# EEZ_DIB_BP3C_r3B3.net
KiCad netlist of a schematic drawn in EAGLE
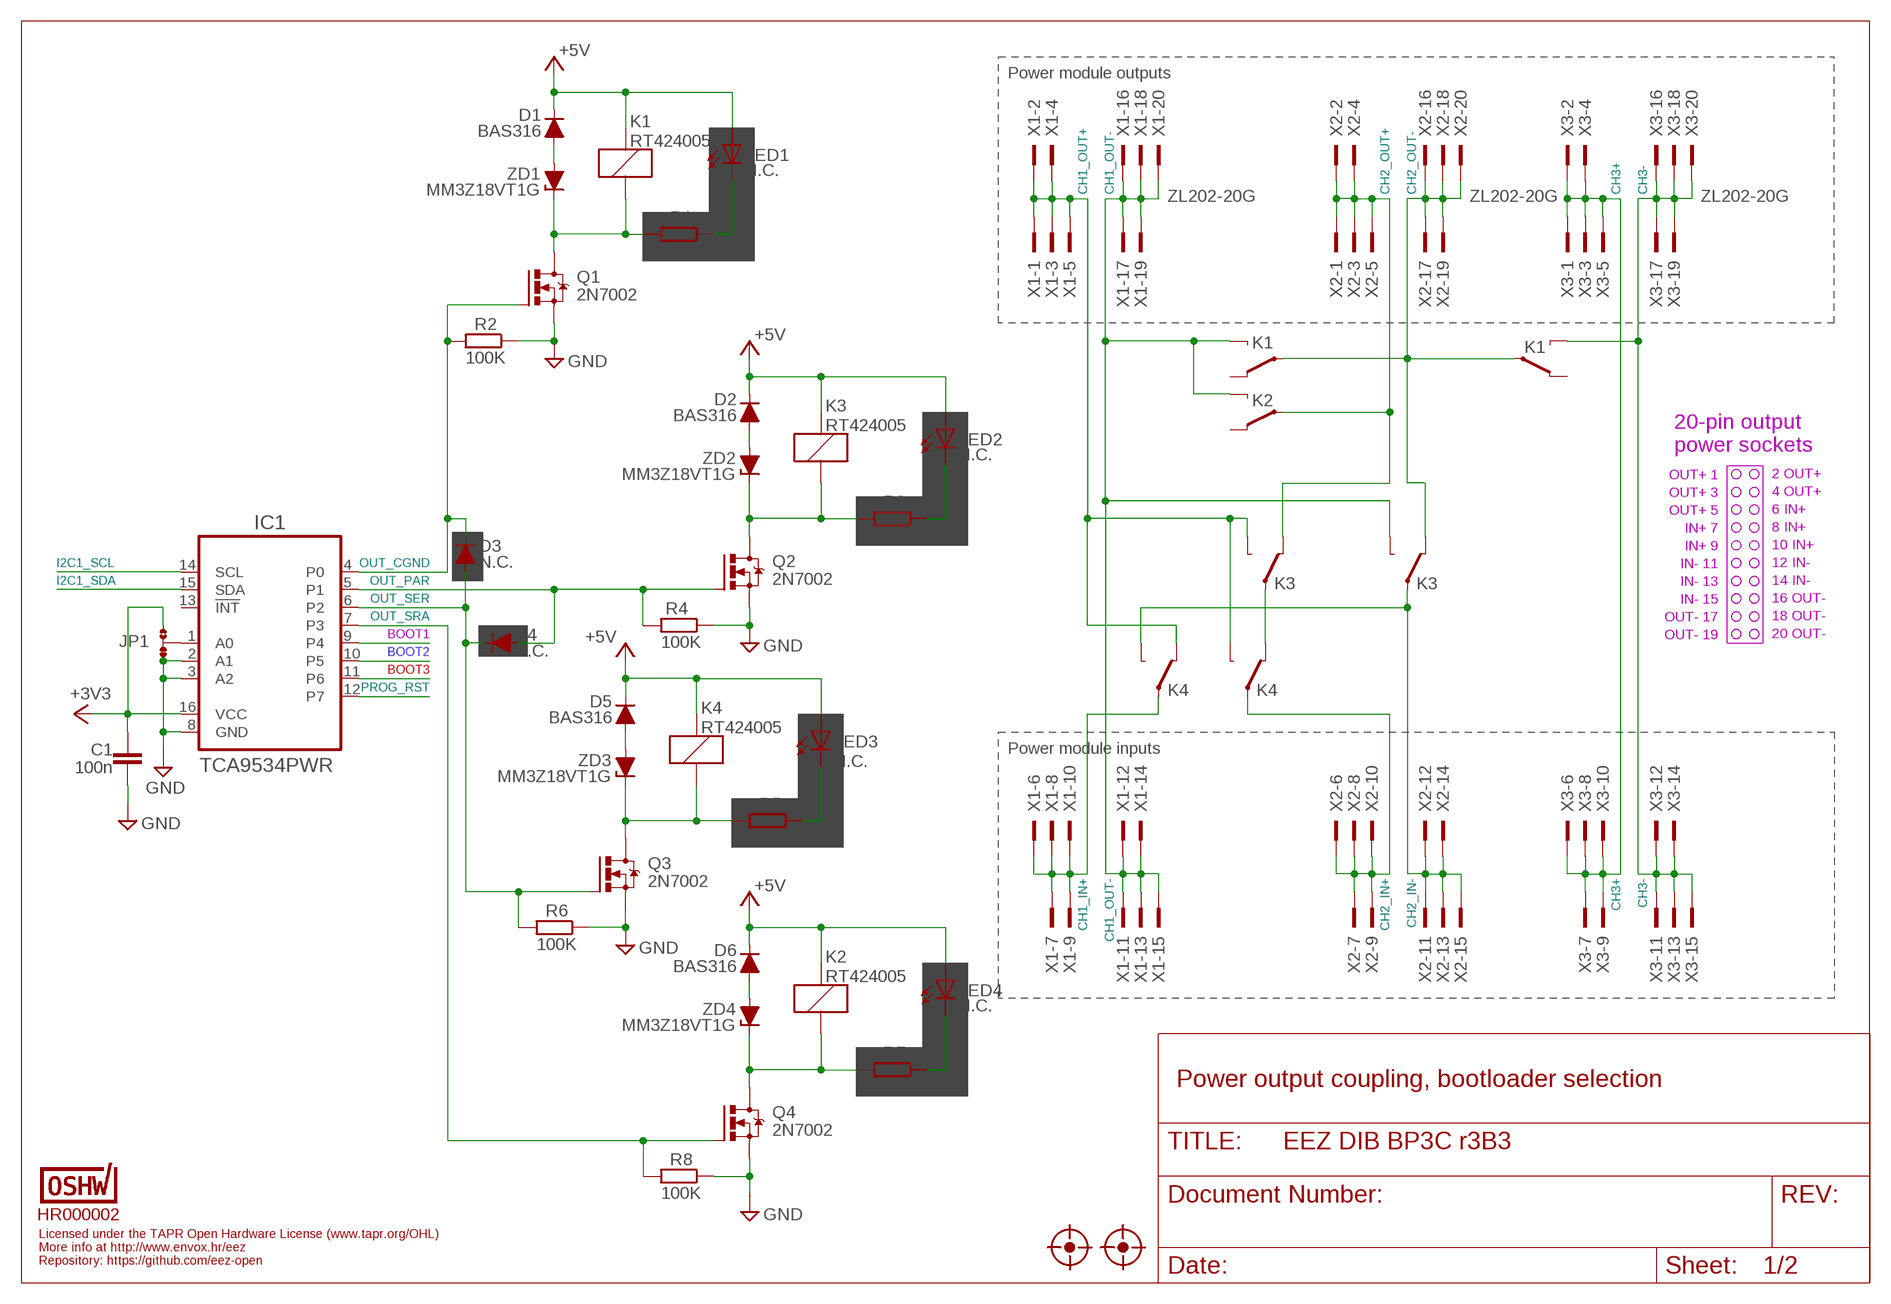
[diagram p0: schematic, sheet 1]
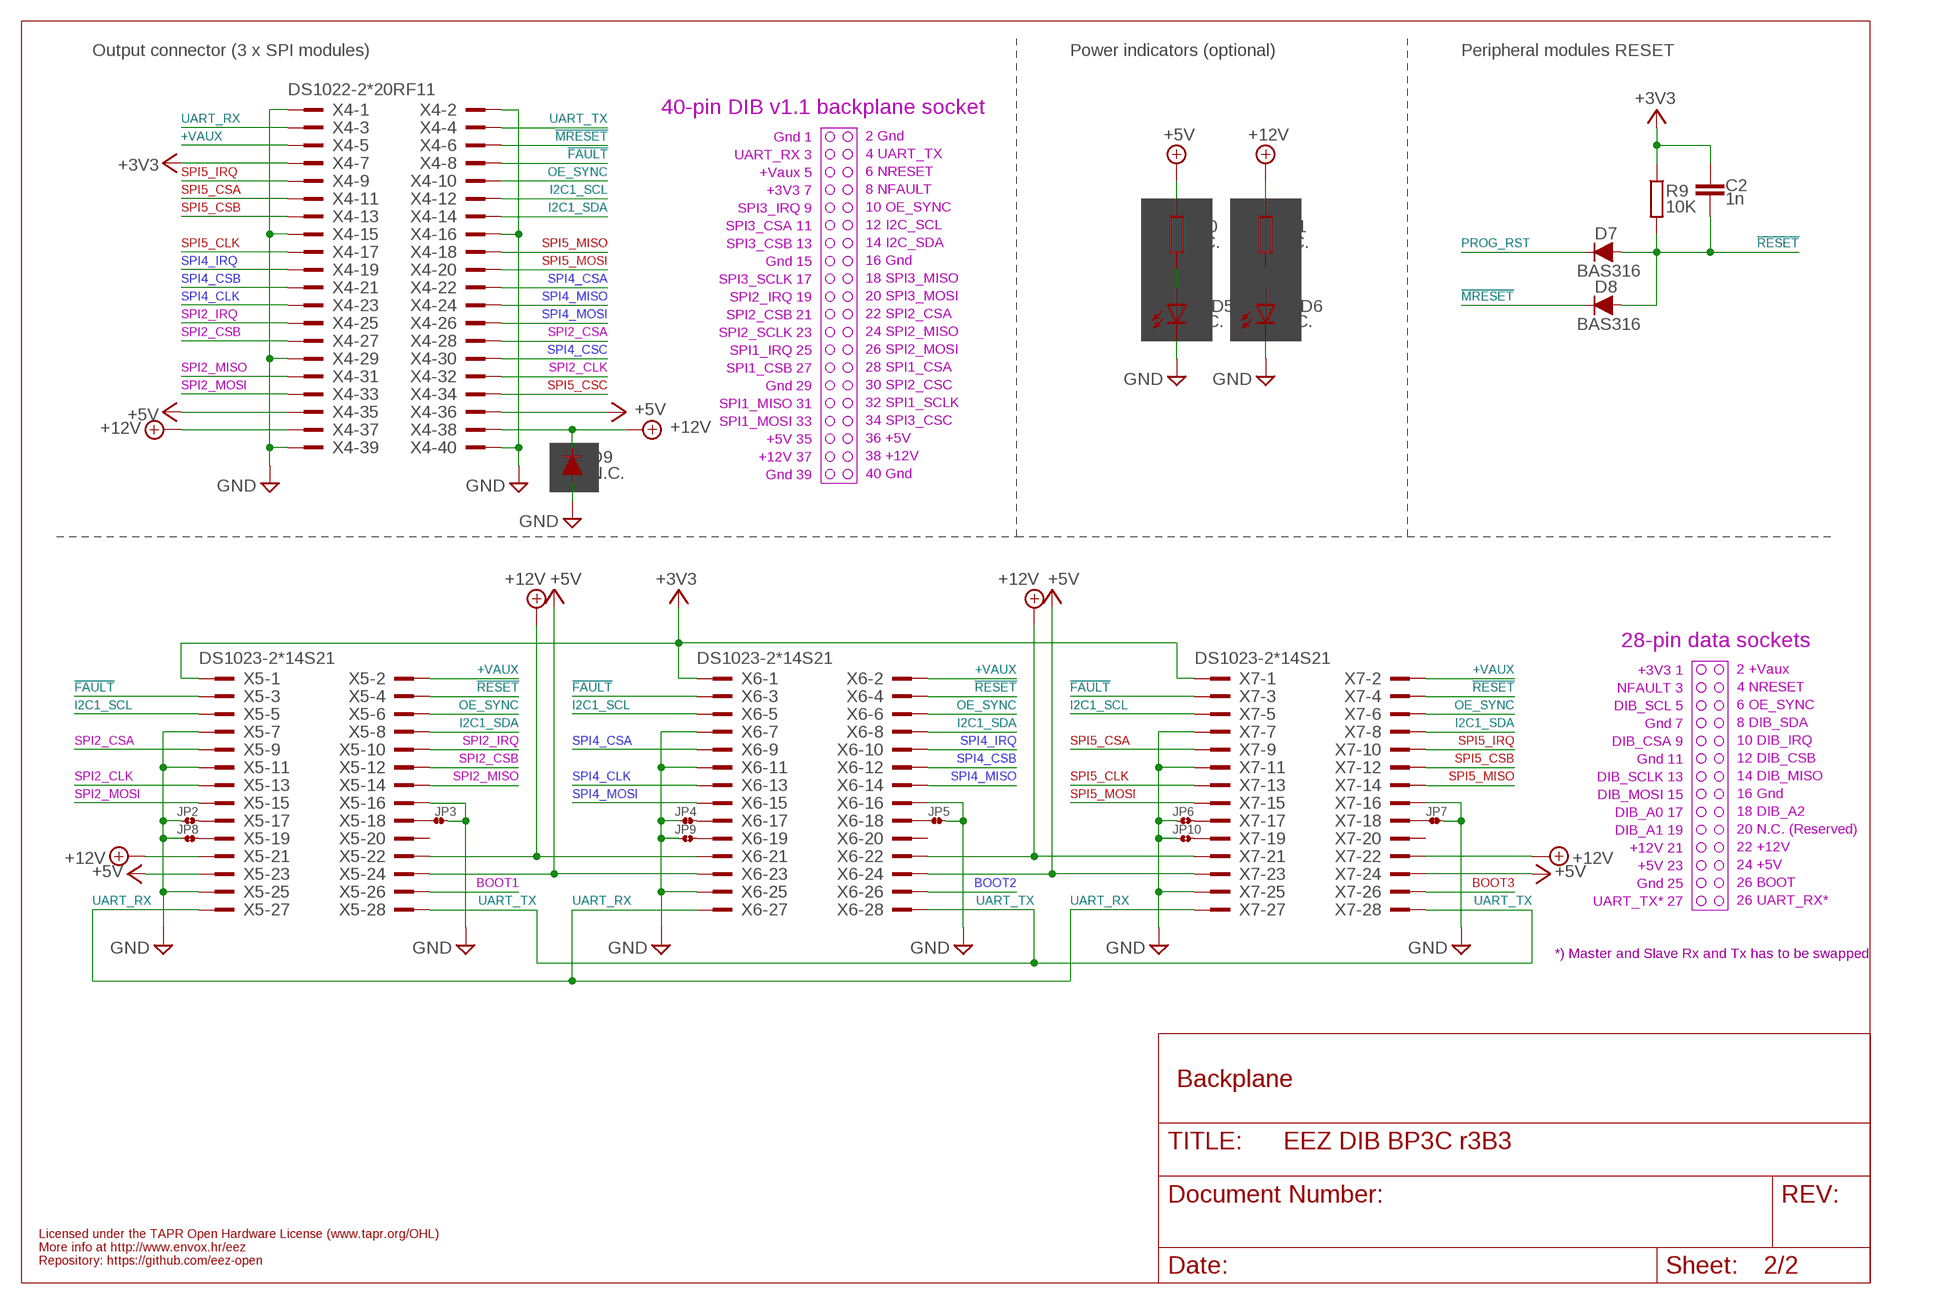
[diagram p1: schematic, sheet 2]

(export (version "E")
  (design (tool "Eeschema 10.0.6"))
  (components
    (comp (ref "C1")
      (value "100n")
      (footprint "eagle-import:C0603")
      (libsource (lib "eagle-import") (part "C-EUC0603"))
    )
    (comp (ref "D1")
      (value "BAS316")
      (footprint "eagle-import:SOD323-R")
      (libsource (lib "eagle-import") (part "DIODESOD323R"))
    )
    (comp (ref "D2")
      (value "BAS316")
      (footprint "eagle-import:SOD323-R")
      (libsource (lib "eagle-import") (part "DIODESOD323R"))
    )
    (comp (ref "D3")
      (value "N.C.")
      (footprint "eagle-import:SOD323-R")
      (libsource (lib "eagle-import") (part "DIODESOD323R"))
    )
    (comp (ref "D4")
      (value "N.C.")
      (footprint "eagle-import:SOD323-R")
      (libsource (lib "eagle-import") (part "DIODESOD323R"))
    )
    (comp (ref "D5")
      (value "BAS316")
      (footprint "eagle-import:SOD323-R")
      (libsource (lib "eagle-import") (part "DIODESOD323R"))
    )
    (comp (ref "D6")
      (value "BAS316")
      (footprint "eagle-import:SOD323-R")
      (libsource (lib "eagle-import") (part "DIODESOD323R"))
    )
    (comp (ref "FM1")
      (value "FIDUCIAL")
      (footprint "eagle-import:FIDUCIAL")
      (libsource (lib "eagle-import") (part "FIDUCIAL"))
    )
    (comp (ref "FM2")
      (value "FIDUCIAL")
      (footprint "eagle-import:FIDUCIAL")
      (libsource (lib "eagle-import") (part "FIDUCIAL"))
    )
    (comp (ref "IC1")
      (value "TCA9534PWR")
      (footprint "eagle-import:PW(R-PDSO-G16)")
      (libsource (lib "eagle-import") (part "TCA9534PWR"))
    )
    (comp (ref "JP1")
      (value "JP3-CUT")
      (footprint "eagle-import:JP3-CUT")
      (libsource (lib "eagle-import") (part "JP3-CUT"))
    )
    (comp (ref "K1")
      (value "RT424005")
      (footprint "eagle-import:RT-C_016A5_ROUND")
      (libsource (lib "eagle-import") (part "RELAY_RT314012-2"))
    )
    (comp (ref "K2")
      (value "RT424005")
      (footprint "eagle-import:RT-C_016A5_ROUND")
      (libsource (lib "eagle-import") (part "RELAY_RT314012-2"))
    )
    (comp (ref "K3")
      (value "RT424005")
      (footprint "eagle-import:RT-C_016A5_ROUND")
      (libsource (lib "eagle-import") (part "RELAY_RT314012-2"))
    )
    (comp (ref "K4")
      (value "RT424005")
      (footprint "eagle-import:RT-C_016A5_ROUND")
      (libsource (lib "eagle-import") (part "RELAY_RT314012-2"))
    )
    (comp (ref "LABEL1")
      (value "HR000002")
      (footprint "eagle-import:CERT-SMALL-SILK")
      (libsource (lib "eagle-import") (part "OSHWA-CERT-SMALL"))
    )
    (comp (ref "LED1")
      (value "N.C.")
      (footprint "eagle-import:LED_0805")
      (libsource (lib "eagle-import") (part "LED0805"))
    )
    (comp (ref "LED2")
      (value "N.C.")
      (footprint "eagle-import:LED_0805")
      (libsource (lib "eagle-import") (part "LED0805"))
    )
    (comp (ref "LED3")
      (value "N.C.")
      (footprint "eagle-import:LED_0805")
      (libsource (lib "eagle-import") (part "LED0805"))
    )
    (comp (ref "LED4")
      (value "N.C.")
      (footprint "eagle-import:LED_0805")
      (libsource (lib "eagle-import") (part "LED0805"))
    )
    (comp (ref "Q1")
      (value "2N7002")
      (footprint "eagle-import:SOT103P240X110-3N")
      (fields
        (field (name "MPN") "2N7002-7-F")
        (field (name "MPN_1") "2N7002-7-F")
        (field (name "OC_FARNELL") "1713823")
        (field (name "OC_NEWARK") "25R5679")
        (field (name "PACKAGE") "SOT-23-3")
        (field (name "SUPPLIER") "DIODES INC.")
      )
      (libsource (lib "eagle-import") (part "2N7002"))
    )
    (comp (ref "Q2")
      (value "2N7002")
      (footprint "eagle-import:SOT103P240X110-3N")
      (fields
        (field (name "MPN") "2N7002-7-F")
        (field (name "MPN_1") "2N7002-7-F")
        (field (name "OC_FARNELL") "1713823")
        (field (name "OC_NEWARK") "25R5679")
        (field (name "PACKAGE") "SOT-23-3")
        (field (name "SUPPLIER") "DIODES INC.")
      )
      (libsource (lib "eagle-import") (part "2N7002"))
    )
    (comp (ref "Q3")
      (value "2N7002")
      (footprint "eagle-import:SOT103P240X110-3N")
      (fields
        (field (name "MPN") "2N7002-7-F")
        (field (name "MPN_1") "2N7002-7-F")
        (field (name "OC_FARNELL") "1713823")
        (field (name "OC_NEWARK") "25R5679")
        (field (name "PACKAGE") "SOT-23-3")
        (field (name "SUPPLIER") "DIODES INC.")
      )
      (libsource (lib "eagle-import") (part "2N7002"))
    )
    (comp (ref "Q4")
      (value "2N7002")
      (footprint "eagle-import:SOT103P240X110-3N")
      (fields
        (field (name "MPN") "2N7002-7-F")
        (field (name "MPN_1") "2N7002-7-F")
        (field (name "OC_FARNELL") "1713823")
        (field (name "OC_NEWARK") "25R5679")
        (field (name "PACKAGE") "SOT-23-3")
        (field (name "SUPPLIER") "DIODES INC.")
      )
      (libsource (lib "eagle-import") (part "2N7002"))
    )
    (comp (ref "R1")
      (value "N.C.")
      (footprint "eagle-import:R0805")
      (libsource (lib "eagle-import") (part "R-EU_R0805"))
    )
    (comp (ref "R2")
      (value "100K")
      (footprint "eagle-import:R0805")
      (libsource (lib "eagle-import") (part "R-EU_R0805"))
    )
    (comp (ref "R3")
      (value "N.C.")
      (footprint "eagle-import:R0805")
      (libsource (lib "eagle-import") (part "R-EU_R0805"))
    )
    (comp (ref "R4")
      (value "100K")
      (footprint "eagle-import:R0805")
      (libsource (lib "eagle-import") (part "R-EU_R0805"))
    )
    (comp (ref "R5")
      (value "N.C.")
      (footprint "eagle-import:R0805")
      (libsource (lib "eagle-import") (part "R-EU_R0805"))
    )
    (comp (ref "R6")
      (value "100K")
      (footprint "eagle-import:R0805")
      (libsource (lib "eagle-import") (part "R-EU_R0805"))
    )
    (comp (ref "R7")
      (value "N.C.")
      (footprint "eagle-import:R0805")
      (libsource (lib "eagle-import") (part "R-EU_R0805"))
    )
    (comp (ref "R8")
      (value "100K")
      (footprint "eagle-import:R0805")
      (libsource (lib "eagle-import") (part "R-EU_R0805"))
    )
    (comp (ref "X1")
      (value "ZL202-20G")
      (footprint "eagle-import:DS1021-2_10SF11")
      (libsource (lib "eagle-import") (part "DS1021-210SF11"))
    )
    (comp (ref "X2")
      (value "ZL202-20G")
      (footprint "eagle-import:DS1021-2_10SF11")
      (libsource (lib "eagle-import") (part "DS1021-210SF11"))
    )
    (comp (ref "X3")
      (value "ZL202-20G")
      (footprint "eagle-import:DS1021-2_10SF11")
      (libsource (lib "eagle-import") (part "DS1021-210SF11"))
    )
    (comp (ref "ZD1")
      (value "MM3Z18VT1G")
      (footprint "eagle-import:SOD323-R")
      (libsource (lib "eagle-import") (part "ZENER-DIODESOD323R"))
    )
    (comp (ref "ZD2")
      (value "MM3Z18VT1G")
      (footprint "eagle-import:SOD323-R")
      (libsource (lib "eagle-import") (part "ZENER-DIODESOD323R"))
    )
    (comp (ref "ZD3")
      (value "MM3Z18VT1G")
      (footprint "eagle-import:SOD323-R")
      (libsource (lib "eagle-import") (part "ZENER-DIODESOD323R"))
    )
    (comp (ref "ZD4")
      (value "MM3Z18VT1G")
      (footprint "eagle-import:SOD323-R")
      (libsource (lib "eagle-import") (part "ZENER-DIODESOD323R"))
    )
    (comp (ref "C2")
      (value "1n")
      (footprint "eagle-import:C0805")
      (libsource (lib "eagle-import") (part "C-EUC0805"))
    )
    (comp (ref "D7")
      (value "BAS316")
      (footprint "eagle-import:SOD323-R")
      (libsource (lib "eagle-import") (part "DIODESOD323R"))
    )
    (comp (ref "D8")
      (value "BAS316")
      (footprint "eagle-import:SOD323-R")
      (libsource (lib "eagle-import") (part "DIODESOD323R"))
    )
    (comp (ref "D9")
      (value "N.C.")
      (footprint "eagle-import:DO214AA")
      (libsource (lib "eagle-import") (part "MyLib6_DIODEDO214AA"))
    )
    (comp (ref "JP2")
      (value "JP2-CUT")
      (footprint "eagle-import:JP2-CUT")
      (libsource (lib "eagle-import") (part "JP2-CUT"))
    )
    (comp (ref "JP3")
      (value "JP2-NOCUT")
      (footprint "eagle-import:JP2-NOCUT")
      (libsource (lib "eagle-import") (part "JP2-NOCUT"))
    )
    (comp (ref "JP4")
      (value "JP2-NOCUT")
      (footprint "eagle-import:JP2-NOCUT")
      (libsource (lib "eagle-import") (part "JP2-NOCUT"))
    )
    (comp (ref "JP5")
      (value "JP2-NOCUT")
      (footprint "eagle-import:JP2-NOCUT")
      (libsource (lib "eagle-import") (part "JP2-NOCUT"))
    )
    (comp (ref "JP6")
      (value "JP2-CUT")
      (footprint "eagle-import:JP2-CUT")
      (libsource (lib "eagle-import") (part "JP2-CUT"))
    )
    (comp (ref "JP7")
      (value "JP2-NOCUT")
      (footprint "eagle-import:JP2-NOCUT")
      (libsource (lib "eagle-import") (part "JP2-NOCUT"))
    )
    (comp (ref "JP8")
      (value "JP2-NOCUT")
      (footprint "eagle-import:JP2-NOCUT")
      (libsource (lib "eagle-import") (part "JP2-NOCUT"))
    )
    (comp (ref "JP9")
      (value "JP2-CUT")
      (footprint "eagle-import:JP2-CUT")
      (libsource (lib "eagle-import") (part "JP2-CUT"))
    )
    (comp (ref "JP10")
      (value "JP2-CUT")
      (footprint "eagle-import:JP2-CUT")
      (libsource (lib "eagle-import") (part "JP2-CUT"))
    )
    (comp (ref "LED5")
      (value "N.C.")
      (footprint "eagle-import:LED_0805")
      (libsource (lib "eagle-import") (part "LED0805"))
    )
    (comp (ref "LED6")
      (value "N.C.")
      (footprint "eagle-import:LED_0805")
      (libsource (lib "eagle-import") (part "LED0805"))
    )
    (comp (ref "R9")
      (value "10K")
      (footprint "eagle-import:R0805")
      (libsource (lib "eagle-import") (part "R-EU_R0805"))
    )
    (comp (ref "R10")
      (value "N.C.")
      (footprint "eagle-import:R0805")
      (libsource (lib "eagle-import") (part "R-EU_R0805"))
    )
    (comp (ref "R11")
      (value "N.C.")
      (footprint "eagle-import:R0805")
      (libsource (lib "eagle-import") (part "R-EU_R0805"))
    )
    (comp (ref "X4")
      (value "DS1022-2*20RF11")
      (footprint "eagle-import:ZL212-40KG")
      (libsource (lib "eagle-import") (part "ZL212-40KG"))
    )
    (comp (ref "X5")
      (value "DS1023-2*14S21")
      (footprint "eagle-import:TSW-114-07-F-D")
      (libsource (lib "eagle-import") (part "TSW-114-07-F-D"))
    )
    (comp (ref "X6")
      (value "DS1023-2*14S21")
      (footprint "eagle-import:TSW-114-07-F-D")
      (libsource (lib "eagle-import") (part "TSW-114-07-F-D"))
    )
    (comp (ref "X7")
      (value "DS1023-2*14S21")
      (footprint "eagle-import:TSW-114-07-F-D")
      (libsource (lib "eagle-import") (part "TSW-114-07-F-D"))
    )
  )
  (nets
    (net (code "1") (name "+3V3") (class "Default")
      (node (ref "C1") (pin "1") (pinfunction "1_1") (pintype "passive"))
      (node (ref "C2") (pin "2") (pinfunction "2_2") (pintype "passive"))
      (node (ref "IC1") (pin "16") (pinfunction "VCC_16") (pintype "passive"))
      (node (ref "JP1") (pin "NO") (pinfunction "NO_NO") (pintype "passive"))
      (node (ref "R9") (pin "1") (pinfunction "1_1") (pintype "passive"))
      (node (ref "X4") (pin "7") (pinfunction "1_7") (pintype "passive"))
      (node (ref "X5") (pin "1") (pinfunction "1_1") (pintype "passive"))
      (node (ref "X6") (pin "1") (pinfunction "1_1") (pintype "passive"))
      (node (ref "X7") (pin "1") (pinfunction "1_1") (pintype "passive"))
    )
    (net (code "2") (name "+5V") (class "Default")
      (node (ref "D1") (pin "C") (pinfunction "C_C") (pintype "passive"))
      (node (ref "D2") (pin "C") (pinfunction "C_C") (pintype "passive"))
      (node (ref "D5") (pin "C") (pinfunction "C_C") (pintype "passive"))
      (node (ref "D6") (pin "C") (pinfunction "C_C") (pintype "passive"))
      (node (ref "K1") (pin "A2") (pinfunction "C1_A2") (pintype "passive"))
      (node (ref "K2") (pin "A2") (pinfunction "C1_A2") (pintype "passive"))
      (node (ref "K3") (pin "A2") (pinfunction "C1_A2") (pintype "passive"))
      (node (ref "K4") (pin "A2") (pinfunction "C1_A2") (pintype "passive"))
      (node (ref "LED1") (pin "A") (pinfunction "A_A") (pintype "passive"))
      (node (ref "LED2") (pin "A") (pinfunction "A_A") (pintype "passive"))
      (node (ref "LED3") (pin "A") (pinfunction "A_A") (pintype "passive"))
      (node (ref "LED4") (pin "A") (pinfunction "A_A") (pintype "passive"))
      (node (ref "R10") (pin "1") (pinfunction "1_1") (pintype "passive"))
      (node (ref "X4") (pin "35") (pinfunction "1_35") (pintype "passive"))
      (node (ref "X4") (pin "36") (pinfunction "1_36") (pintype "passive"))
      (node (ref "X5") (pin "23") (pinfunction "1_23") (pintype "passive"))
      (node (ref "X5") (pin "24") (pinfunction "1_24") (pintype "passive"))
      (node (ref "X6") (pin "23") (pinfunction "1_23") (pintype "passive"))
      (node (ref "X6") (pin "24") (pinfunction "1_24") (pintype "passive"))
      (node (ref "X7") (pin "23") (pinfunction "1_23") (pintype "passive"))
      (node (ref "X7") (pin "24") (pinfunction "1_24") (pintype "passive"))
    )
    (net (code "3") (name "+12V") (class "Default")
      (node (ref "D9") (pin "C") (pinfunction "C_C") (pintype "passive"))
      (node (ref "R11") (pin "1") (pinfunction "1_1") (pintype "passive"))
      (node (ref "X4") (pin "37") (pinfunction "1_37") (pintype "passive"))
      (node (ref "X4") (pin "38") (pinfunction "1_38") (pintype "passive"))
      (node (ref "X5") (pin "21") (pinfunction "1_21") (pintype "passive"))
      (node (ref "X5") (pin "22") (pinfunction "1_22") (pintype "passive"))
      (node (ref "X6") (pin "21") (pinfunction "1_21") (pintype "passive"))
      (node (ref "X6") (pin "22") (pinfunction "1_22") (pintype "passive"))
      (node (ref "X7") (pin "21") (pinfunction "1_21") (pintype "passive"))
      (node (ref "X7") (pin "22") (pinfunction "1_22") (pintype "passive"))
    )
    (net (code "4") (name "+VAUX") (class "Default")
      (node (ref "X4") (pin "5") (pinfunction "1_5") (pintype "passive"))
      (node (ref "X5") (pin "2") (pinfunction "1_2") (pintype "passive"))
      (node (ref "X6") (pin "2") (pinfunction "1_2") (pintype "passive"))
      (node (ref "X7") (pin "2") (pinfunction "1_2") (pintype "passive"))
    )
    (net (code "5") (name "BOOT1") (class "Default")
      (node (ref "IC1") (pin "9") (pinfunction "P4_9") (pintype "bidirectional"))
      (node (ref "X5") (pin "26") (pinfunction "1_26") (pintype "passive"))
    )
    (net (code "6") (name "BOOT2") (class "Default")
      (node (ref "IC1") (pin "10") (pinfunction "P5_10") (pintype "bidirectional"))
      (node (ref "X6") (pin "26") (pinfunction "1_26") (pintype "passive"))
    )
    (net (code "7") (name "BOOT3") (class "Default")
      (node (ref "IC1") (pin "11") (pinfunction "P6_11") (pintype "bidirectional"))
      (node (ref "X7") (pin "26") (pinfunction "1_26") (pintype "passive"))
    )
    (net (code "8") (name "CH1_IN+") (class "Default")
      (node (ref "K4") (pin "11A") (pinfunction "P_11A") (pintype "passive"))
      (node (ref "X1") (pin "10") (pinfunction "1_10") (pintype "passive"))
      (node (ref "X1") (pin "6") (pinfunction "1_6") (pintype "passive"))
      (node (ref "X1") (pin "7") (pinfunction "1_7") (pintype "passive"))
      (node (ref "X1") (pin "8") (pinfunction "1_8") (pintype "passive"))
      (node (ref "X1") (pin "9") (pinfunction "1_9") (pintype "passive"))
    )
    (net (code "9") (name "CH1_OUT+") (class "Default")
      (node (ref "K3") (pin "14A") (pinfunction "O_14A") (pintype "passive"))
      (node (ref "K4") (pin "12A") (pinfunction "S_12A") (pintype "passive"))
      (node (ref "K4") (pin "14B") (pinfunction "O_14B") (pintype "passive"))
      (node (ref "X1") (pin "1") (pinfunction "1_1") (pintype "passive"))
      (node (ref "X1") (pin "2") (pinfunction "1_2") (pintype "passive"))
      (node (ref "X1") (pin "3") (pinfunction "1_3") (pintype "passive"))
      (node (ref "X1") (pin "4") (pinfunction "1_4") (pintype "passive"))
      (node (ref "X1") (pin "5") (pinfunction "1_5") (pintype "passive"))
    )
    (net (code "10") (name "CH1_OUT-") (class "Default")
      (node (ref "K1") (pin "14A") (pinfunction "O_14A") (pintype "passive"))
      (node (ref "K2") (pin "14A") (pinfunction "O_14A") (pintype "passive"))
      (node (ref "K3") (pin "14B") (pinfunction "O_14B") (pintype "passive"))
      (node (ref "X1") (pin "11") (pinfunction "1_11") (pintype "passive"))
      (node (ref "X1") (pin "12") (pinfunction "1_12") (pintype "passive"))
      (node (ref "X1") (pin "13") (pinfunction "1_13") (pintype "passive"))
      (node (ref "X1") (pin "14") (pinfunction "1_14") (pintype "passive"))
      (node (ref "X1") (pin "15") (pinfunction "1_15") (pintype "passive"))
      (node (ref "X1") (pin "16") (pinfunction "1_16") (pintype "passive"))
      (node (ref "X1") (pin "17") (pinfunction "1_17") (pintype "passive"))
      (node (ref "X1") (pin "18") (pinfunction "1_18") (pintype "passive"))
      (node (ref "X1") (pin "19") (pinfunction "1_19") (pintype "passive"))
      (node (ref "X1") (pin "20") (pinfunction "1_20") (pintype "passive"))
    )
    (net (code "11") (name "CH2_IN+") (class "Default")
      (node (ref "K4") (pin "11B") (pinfunction "P_11B") (pintype "passive"))
      (node (ref "X2") (pin "10") (pinfunction "1_10") (pintype "passive"))
      (node (ref "X2") (pin "6") (pinfunction "1_6") (pintype "passive"))
      (node (ref "X2") (pin "7") (pinfunction "1_7") (pintype "passive"))
      (node (ref "X2") (pin "8") (pinfunction "1_8") (pintype "passive"))
      (node (ref "X2") (pin "9") (pinfunction "1_9") (pintype "passive"))
    )
    (net (code "12") (name "CH2_IN-") (class "Default")
      (node (ref "K3") (pin "11B") (pinfunction "P_11B") (pintype "passive"))
      (node (ref "K4") (pin "14A") (pinfunction "O_14A") (pintype "passive"))
      (node (ref "X2") (pin "11") (pinfunction "1_11") (pintype "passive"))
      (node (ref "X2") (pin "12") (pinfunction "1_12") (pintype "passive"))
      (node (ref "X2") (pin "13") (pinfunction "1_13") (pintype "passive"))
      (node (ref "X2") (pin "14") (pinfunction "1_14") (pintype "passive"))
      (node (ref "X2") (pin "15") (pinfunction "1_15") (pintype "passive"))
    )
    (net (code "13") (name "CH2_OUT+") (class "Default")
      (node (ref "K2") (pin "11A") (pinfunction "P_11A") (pintype "passive"))
      (node (ref "K3") (pin "12A") (pinfunction "S_12A") (pintype "passive"))
      (node (ref "X2") (pin "1") (pinfunction "1_1") (pintype "passive"))
      (node (ref "X2") (pin "2") (pinfunction "1_2") (pintype "passive"))
      (node (ref "X2") (pin "3") (pinfunction "1_3") (pintype "passive"))
      (node (ref "X2") (pin "4") (pinfunction "1_4") (pintype "passive"))
      (node (ref "X2") (pin "5") (pinfunction "1_5") (pintype "passive"))
    )
    (net (code "14") (name "CH2_OUT-") (class "Default")
      (node (ref "K1") (pin "11A") (pinfunction "P_11A") (pintype "passive"))
      (node (ref "K1") (pin "11B") (pinfunction "P_11B") (pintype "passive"))
      (node (ref "K3") (pin "12B") (pinfunction "S_12B") (pintype "passive"))
      (node (ref "X2") (pin "16") (pinfunction "1_16") (pintype "passive"))
      (node (ref "X2") (pin "17") (pinfunction "1_17") (pintype "passive"))
      (node (ref "X2") (pin "18") (pinfunction "1_18") (pintype "passive"))
      (node (ref "X2") (pin "19") (pinfunction "1_19") (pintype "passive"))
      (node (ref "X2") (pin "20") (pinfunction "1_20") (pintype "passive"))
    )
    (net (code "15") (name "CH3+") (class "Default")
      (node (ref "X3") (pin "1") (pinfunction "1_1") (pintype "passive"))
      (node (ref "X3") (pin "10") (pinfunction "1_10") (pintype "passive"))
      (node (ref "X3") (pin "2") (pinfunction "1_2") (pintype "passive"))
      (node (ref "X3") (pin "3") (pinfunction "1_3") (pintype "passive"))
      (node (ref "X3") (pin "4") (pinfunction "1_4") (pintype "passive"))
      (node (ref "X3") (pin "5") (pinfunction "1_5") (pintype "passive"))
      (node (ref "X3") (pin "6") (pinfunction "1_6") (pintype "passive"))
      (node (ref "X3") (pin "7") (pinfunction "1_7") (pintype "passive"))
      (node (ref "X3") (pin "8") (pinfunction "1_8") (pintype "passive"))
      (node (ref "X3") (pin "9") (pinfunction "1_9") (pintype "passive"))
    )
    (net (code "16") (name "CH3-") (class "Default")
      (node (ref "K1") (pin "14B") (pinfunction "O_14B") (pintype "passive"))
      (node (ref "X3") (pin "11") (pinfunction "1_11") (pintype "passive"))
      (node (ref "X3") (pin "12") (pinfunction "1_12") (pintype "passive"))
      (node (ref "X3") (pin "13") (pinfunction "1_13") (pintype "passive"))
      (node (ref "X3") (pin "14") (pinfunction "1_14") (pintype "passive"))
      (node (ref "X3") (pin "15") (pinfunction "1_15") (pintype "passive"))
      (node (ref "X3") (pin "16") (pinfunction "1_16") (pintype "passive"))
      (node (ref "X3") (pin "17") (pinfunction "1_17") (pintype "passive"))
      (node (ref "X3") (pin "18") (pinfunction "1_18") (pintype "passive"))
      (node (ref "X3") (pin "19") (pinfunction "1_19") (pintype "passive"))
      (node (ref "X3") (pin "20") (pinfunction "1_20") (pintype "passive"))
    )
    (net (code "17") (name "GND") (class "Default")
      (node (ref "C1") (pin "2") (pinfunction "2_2") (pintype "passive"))
      (node (ref "D9") (pin "A") (pinfunction "A_A") (pintype "passive"))
      (node (ref "IC1") (pin "2") (pinfunction "A1_2") (pintype "input"))
      (node (ref "IC1") (pin "3") (pinfunction "A2_3") (pintype "input"))
      (node (ref "IC1") (pin "8") (pinfunction "GND_8") (pintype "passive"))
      (node (ref "JP1") (pin "NC") (pinfunction "NC_NC") (pintype "passive"))
      (node (ref "JP10") (pin "1") (pinfunction "1_1") (pintype "passive"))
      (node (ref "JP2") (pin "1") (pinfunction "1_1") (pintype "passive"))
      (node (ref "JP3") (pin "2") (pinfunction "2_2") (pintype "passive"))
      (node (ref "JP4") (pin "1") (pinfunction "1_1") (pintype "passive"))
      (node (ref "JP5") (pin "2") (pinfunction "2_2") (pintype "passive"))
      (node (ref "JP6") (pin "1") (pinfunction "1_1") (pintype "passive"))
      (node (ref "JP7") (pin "2") (pinfunction "2_2") (pintype "passive"))
      (node (ref "JP8") (pin "1") (pinfunction "1_1") (pintype "passive"))
      (node (ref "JP9") (pin "1") (pinfunction "1_1") (pintype "passive"))
      (node (ref "LED5") (pin "C") (pinfunction "C_C") (pintype "passive"))
      (node (ref "LED6") (pin "C") (pinfunction "C_C") (pintype "passive"))
      (node (ref "Q1") (pin "2") (pinfunction "S_2") (pintype "passive"))
      (node (ref "Q2") (pin "2") (pinfunction "S_2") (pintype "passive"))
      (node (ref "Q3") (pin "2") (pinfunction "S_2") (pintype "passive"))
      (node (ref "Q4") (pin "2") (pinfunction "S_2") (pintype "passive"))
      (node (ref "R2") (pin "1") (pinfunction "1_1") (pintype "passive"))
      (node (ref "R4") (pin "1") (pinfunction "1_1") (pintype "passive"))
      (node (ref "R6") (pin "1") (pinfunction "1_1") (pintype "passive"))
      (node (ref "R8") (pin "1") (pinfunction "1_1") (pintype "passive"))
      (node (ref "X4") (pin "1") (pinfunction "1_1") (pintype "passive"))
      (node (ref "X4") (pin "15") (pinfunction "1_15") (pintype "passive"))
      (node (ref "X4") (pin "16") (pinfunction "1_16") (pintype "passive"))
      (node (ref "X4") (pin "2") (pinfunction "1_2") (pintype "passive"))
      (node (ref "X4") (pin "29") (pinfunction "1_29") (pintype "passive"))
      (node (ref "X4") (pin "39") (pinfunction "1_39") (pintype "passive"))
      (node (ref "X4") (pin "40") (pinfunction "1_40") (pintype "passive"))
      (node (ref "X5") (pin "11") (pinfunction "1_11") (pintype "passive"))
      (node (ref "X5") (pin "16") (pinfunction "1_16") (pintype "passive"))
      (node (ref "X5") (pin "25") (pinfunction "1_25") (pintype "passive"))
      (node (ref "X5") (pin "7") (pinfunction "1_7") (pintype "passive"))
      (node (ref "X6") (pin "11") (pinfunction "1_11") (pintype "passive"))
      (node (ref "X6") (pin "16") (pinfunction "1_16") (pintype "passive"))
      (node (ref "X6") (pin "25") (pinfunction "1_25") (pintype "passive"))
      (node (ref "X6") (pin "7") (pinfunction "1_7") (pintype "passive"))
      (node (ref "X7") (pin "11") (pinfunction "1_11") (pintype "passive"))
      (node (ref "X7") (pin "16") (pinfunction "1_16") (pintype "passive"))
      (node (ref "X7") (pin "25") (pinfunction "1_25") (pintype "passive"))
      (node (ref "X7") (pin "7") (pinfunction "1_7") (pintype "passive"))
    )
    (net (code "18") (name "I2C1_SCL") (class "Default")
      (node (ref "IC1") (pin "14") (pinfunction "SCL_14") (pintype "input"))
      (node (ref "X4") (pin "12") (pinfunction "1_12") (pintype "passive"))
      (node (ref "X5") (pin "5") (pinfunction "1_5") (pintype "passive"))
      (node (ref "X6") (pin "5") (pinfunction "1_5") (pintype "passive"))
      (node (ref "X7") (pin "5") (pinfunction "1_5") (pintype "passive"))
    )
    (net (code "19") (name "I2C1_SDA") (class "Default")
      (node (ref "IC1") (pin "15") (pinfunction "SDA_15") (pintype "bidirectional"))
      (node (ref "X4") (pin "14") (pinfunction "1_14") (pintype "passive"))
      (node (ref "X5") (pin "8") (pinfunction "1_8") (pintype "passive"))
      (node (ref "X6") (pin "8") (pinfunction "1_8") (pintype "passive"))
      (node (ref "X7") (pin "8") (pinfunction "1_8") (pintype "passive"))
    )
    (net (code "20") (name "Net-(D1-PadA)") (class "Default")
      (node (ref "D1") (pin "A") (pinfunction "A_A") (pintype "passive"))
      (node (ref "ZD1") (pin "A") (pinfunction "A_A") (pintype "passive"))
    )
    (net (code "21") (name "Net-(D2-PadA)") (class "Default")
      (node (ref "D2") (pin "A") (pinfunction "A_A") (pintype "passive"))
      (node (ref "ZD2") (pin "A") (pinfunction "A_A") (pintype "passive"))
    )
    (net (code "22") (name "Net-(D5-PadA)") (class "Default")
      (node (ref "D5") (pin "A") (pinfunction "A_A") (pintype "passive"))
      (node (ref "ZD3") (pin "A") (pinfunction "A_A") (pintype "passive"))
    )
    (net (code "23") (name "Net-(D6-PadA)") (class "Default")
      (node (ref "D6") (pin "A") (pinfunction "A_A") (pintype "passive"))
      (node (ref "ZD4") (pin "A") (pinfunction "A_A") (pintype "passive"))
    )
    (net (code "24") (name "Net-(IC1-A0)") (class "Default")
      (node (ref "IC1") (pin "1") (pinfunction "A0_1") (pintype "input"))
      (node (ref "JP1") (pin "COM") (pinfunction "COM_COM") (pintype "passive"))
    )
    (net (code "25") (name "Net-(K1C-C2)") (class "Default")
      (node (ref "K1") (pin "A1") (pinfunction "C2_A1") (pintype "passive"))
      (node (ref "Q1") (pin "3") (pinfunction "D_3") (pintype "passive"))
      (node (ref "R1") (pin "2") (pinfunction "2_2") (pintype "passive"))
      (node (ref "ZD1") (pin "C") (pinfunction "C_C") (pintype "passive"))
    )
    (net (code "26") (name "Net-(K2C-C2)") (class "Default")
      (node (ref "K2") (pin "A1") (pinfunction "C2_A1") (pintype "passive"))
      (node (ref "Q4") (pin "3") (pinfunction "D_3") (pintype "passive"))
      (node (ref "R7") (pin "2") (pinfunction "2_2") (pintype "passive"))
      (node (ref "ZD4") (pin "C") (pinfunction "C_C") (pintype "passive"))
    )
    (net (code "27") (name "Net-(K3A-P)") (class "Default")
      (node (ref "K3") (pin "11A") (pinfunction "P_11A") (pintype "passive"))
      (node (ref "K4") (pin "12B") (pinfunction "S_12B") (pintype "passive"))
    )
    (net (code "28") (name "Net-(K3C-C2)") (class "Default")
      (node (ref "K3") (pin "A1") (pinfunction "C2_A1") (pintype "passive"))
      (node (ref "Q2") (pin "3") (pinfunction "D_3") (pintype "passive"))
      (node (ref "R3") (pin "2") (pinfunction "2_2") (pintype "passive"))
      (node (ref "ZD2") (pin "C") (pinfunction "C_C") (pintype "passive"))
    )
    (net (code "29") (name "Net-(K4C-C2)") (class "Default")
      (node (ref "K4") (pin "A1") (pinfunction "C2_A1") (pintype "passive"))
      (node (ref "Q3") (pin "3") (pinfunction "D_3") (pintype "passive"))
      (node (ref "R5") (pin "2") (pinfunction "2_2") (pintype "passive"))
      (node (ref "ZD3") (pin "C") (pinfunction "C_C") (pintype "passive"))
    )
    (net (code "30") (name "Net-(LED1-PadC)") (class "Default")
      (node (ref "LED1") (pin "C") (pinfunction "C_C") (pintype "passive"))
      (node (ref "R1") (pin "1") (pinfunction "1_1") (pintype "passive"))
    )
    (net (code "31") (name "Net-(LED2-PadC)") (class "Default")
      (node (ref "LED2") (pin "C") (pinfunction "C_C") (pintype "passive"))
      (node (ref "R3") (pin "1") (pinfunction "1_1") (pintype "passive"))
    )
    (net (code "32") (name "Net-(LED3-PadC)") (class "Default")
      (node (ref "LED3") (pin "C") (pinfunction "C_C") (pintype "passive"))
      (node (ref "R5") (pin "1") (pinfunction "1_1") (pintype "passive"))
    )
    (net (code "33") (name "Net-(LED4-PadC)") (class "Default")
      (node (ref "LED4") (pin "C") (pinfunction "C_C") (pintype "passive"))
      (node (ref "R7") (pin "1") (pinfunction "1_1") (pintype "passive"))
    )
    (net (code "34") (name "Net-(LED5-PadA)") (class "Default")
      (node (ref "LED5") (pin "A") (pinfunction "A_A") (pintype "passive"))
      (node (ref "R10") (pin "2") (pinfunction "2_2") (pintype "passive"))
    )
    (net (code "35") (name "Net-(LED6-PadA)") (class "Default")
      (node (ref "LED6") (pin "A") (pinfunction "A_A") (pintype "passive"))
      (node (ref "R11") (pin "2") (pinfunction "2_2") (pintype "passive"))
    )
    (net (code "36") (name "Net-(X5I-1)") (class "Default")
      (node (ref "JP2") (pin "2") (pinfunction "2_2") (pintype "passive"))
      (node (ref "X5") (pin "17") (pinfunction "1_17") (pintype "passive"))
    )
    (net (code "37") (name "Net-(X5J-1)") (class "Default")
      (node (ref "JP3") (pin "1") (pinfunction "1_1") (pintype "passive"))
      (node (ref "X5") (pin "18") (pinfunction "1_18") (pintype "passive"))
    )
    (net (code "38") (name "Net-(X5K-1)") (class "Default")
      (node (ref "JP8") (pin "2") (pinfunction "2_2") (pintype "passive"))
      (node (ref "X5") (pin "19") (pinfunction "1_19") (pintype "passive"))
    )
    (net (code "39") (name "Net-(X6I-1)") (class "Default")
      (node (ref "JP4") (pin "2") (pinfunction "2_2") (pintype "passive"))
      (node (ref "X6") (pin "17") (pinfunction "1_17") (pintype "passive"))
    )
    (net (code "40") (name "Net-(X6J-1)") (class "Default")
      (node (ref "JP5") (pin "1") (pinfunction "1_1") (pintype "passive"))
      (node (ref "X6") (pin "18") (pinfunction "1_18") (pintype "passive"))
    )
    (net (code "41") (name "Net-(X6K-1)") (class "Default")
      (node (ref "JP9") (pin "2") (pinfunction "2_2") (pintype "passive"))
      (node (ref "X6") (pin "19") (pinfunction "1_19") (pintype "passive"))
    )
    (net (code "42") (name "Net-(X7I-1)") (class "Default")
      (node (ref "JP6") (pin "2") (pinfunction "2_2") (pintype "passive"))
      (node (ref "X7") (pin "17") (pinfunction "1_17") (pintype "passive"))
    )
    (net (code "43") (name "Net-(X7J-1)") (class "Default")
      (node (ref "JP7") (pin "1") (pinfunction "1_1") (pintype "passive"))
      (node (ref "X7") (pin "18") (pinfunction "1_18") (pintype "passive"))
    )
    (net (code "44") (name "Net-(X7K-1)") (class "Default")
      (node (ref "JP10") (pin "2") (pinfunction "2_2") (pintype "passive"))
      (node (ref "X7") (pin "19") (pinfunction "1_19") (pintype "passive"))
    )
    (net (code "45") (name "OE_SYNC") (class "Default")
      (node (ref "X4") (pin "10") (pinfunction "1_10") (pintype "passive"))
      (node (ref "X5") (pin "6") (pinfunction "1_6") (pintype "passive"))
      (node (ref "X6") (pin "6") (pinfunction "1_6") (pintype "passive"))
      (node (ref "X7") (pin "6") (pinfunction "1_6") (pintype "passive"))
    )
    (net (code "46") (name "OUT_CGND") (class "Default")
      (node (ref "D3") (pin "C") (pinfunction "C_C") (pintype "passive"))
      (node (ref "IC1") (pin "4") (pinfunction "P0_4") (pintype "bidirectional"))
      (node (ref "Q1") (pin "1") (pinfunction "G_1") (pintype "passive"))
      (node (ref "R2") (pin "2") (pinfunction "2_2") (pintype "passive"))
    )
    (net (code "47") (name "OUT_PAR") (class "Default")
      (node (ref "D4") (pin "A") (pinfunction "A_A") (pintype "passive"))
      (node (ref "IC1") (pin "5") (pinfunction "P1_5") (pintype "bidirectional"))
      (node (ref "Q2") (pin "1") (pinfunction "G_1") (pintype "passive"))
      (node (ref "R4") (pin "2") (pinfunction "2_2") (pintype "passive"))
    )
    (net (code "48") (name "OUT_SER") (class "Default")
      (node (ref "D3") (pin "A") (pinfunction "A_A") (pintype "passive"))
      (node (ref "D4") (pin "C") (pinfunction "C_C") (pintype "passive"))
      (node (ref "IC1") (pin "6") (pinfunction "P2_6") (pintype "bidirectional"))
      (node (ref "Q3") (pin "1") (pinfunction "G_1") (pintype "passive"))
      (node (ref "R6") (pin "2") (pinfunction "2_2") (pintype "passive"))
    )
    (net (code "49") (name "OUT_SRA") (class "Default")
      (node (ref "IC1") (pin "7") (pinfunction "P3_7") (pintype "bidirectional"))
      (node (ref "Q4") (pin "1") (pinfunction "G_1") (pintype "passive"))
      (node (ref "R8") (pin "2") (pinfunction "2_2") (pintype "passive"))
    )
    (net (code "50") (name "PROG_RST") (class "Default")
      (node (ref "D7") (pin "C") (pinfunction "C_C") (pintype "passive"))
      (node (ref "IC1") (pin "12") (pinfunction "P7_12") (pintype "bidirectional"))
    )
    (net (code "51") (name "SPI2_CLK") (class "Default")
      (node (ref "X4") (pin "32") (pinfunction "1_32") (pintype "passive"))
      (node (ref "X5") (pin "13") (pinfunction "1_13") (pintype "passive"))
    )
    (net (code "52") (name "SPI2_CSA") (class "Default")
      (node (ref "X4") (pin "28") (pinfunction "1_28") (pintype "passive"))
      (node (ref "X5") (pin "9") (pinfunction "1_9") (pintype "passive"))
    )
    (net (code "53") (name "SPI2_CSB") (class "Default")
      (node (ref "X4") (pin "27") (pinfunction "1_27") (pintype "passive"))
      (node (ref "X5") (pin "12") (pinfunction "1_12") (pintype "passive"))
    )
    (net (code "54") (name "SPI2_IRQ") (class "Default")
      (node (ref "X4") (pin "25") (pinfunction "1_25") (pintype "passive"))
      (node (ref "X5") (pin "10") (pinfunction "1_10") (pintype "passive"))
    )
    (net (code "55") (name "SPI2_MISO") (class "Default")
      (node (ref "X4") (pin "31") (pinfunction "1_31") (pintype "passive"))
      (node (ref "X5") (pin "14") (pinfunction "1_14") (pintype "passive"))
    )
    (net (code "56") (name "SPI2_MOSI") (class "Default")
      (node (ref "X4") (pin "33") (pinfunction "1_33") (pintype "passive"))
      (node (ref "X5") (pin "15") (pinfunction "1_15") (pintype "passive"))
    )
    (net (code "57") (name "SPI4_CLK") (class "Default")
      (node (ref "X4") (pin "23") (pinfunction "1_23") (pintype "passive"))
      (node (ref "X6") (pin "13") (pinfunction "1_13") (pintype "passive"))
    )
    (net (code "58") (name "SPI4_CSA") (class "Default")
      (node (ref "X4") (pin "22") (pinfunction "1_22") (pintype "passive"))
      (node (ref "X6") (pin "9") (pinfunction "1_9") (pintype "passive"))
    )
    (net (code "59") (name "SPI4_CSB") (class "Default")
      (node (ref "X4") (pin "21") (pinfunction "1_21") (pintype "passive"))
      (node (ref "X6") (pin "12") (pinfunction "1_12") (pintype "passive"))
    )
    (net (code "60") (name "SPI4_CSC") (class "Default")
      (node (ref "X4") (pin "30") (pinfunction "1_30") (pintype "passive"))
    )
    (net (code "61") (name "SPI4_IRQ") (class "Default")
      (node (ref "X4") (pin "19") (pinfunction "1_19") (pintype "passive"))
      (node (ref "X6") (pin "10") (pinfunction "1_10") (pintype "passive"))
    )
    (net (code "62") (name "SPI4_MISO") (class "Default")
      (node (ref "X4") (pin "24") (pinfunction "1_24") (pintype "passive"))
      (node (ref "X6") (pin "14") (pinfunction "1_14") (pintype "passive"))
    )
    (net (code "63") (name "SPI4_MOSI") (class "Default")
      (node (ref "X4") (pin "26") (pinfunction "1_26") (pintype "passive"))
      (node (ref "X6") (pin "15") (pinfunction "1_15") (pintype "passive"))
    )
    (net (code "64") (name "SPI5_CLK") (class "Default")
      (node (ref "X4") (pin "17") (pinfunction "1_17") (pintype "passive"))
      (node (ref "X7") (pin "13") (pinfunction "1_13") (pintype "passive"))
    )
    (net (code "65") (name "SPI5_CSA") (class "Default")
      (node (ref "X4") (pin "11") (pinfunction "1_11") (pintype "passive"))
      (node (ref "X7") (pin "9") (pinfunction "1_9") (pintype "passive"))
    )
    (net (code "66") (name "SPI5_CSB") (class "Default")
      (node (ref "X4") (pin "13") (pinfunction "1_13") (pintype "passive"))
      (node (ref "X7") (pin "12") (pinfunction "1_12") (pintype "passive"))
    )
    (net (code "67") (name "SPI5_CSC") (class "Default")
      (node (ref "X4") (pin "34") (pinfunction "1_34") (pintype "passive"))
    )
    (net (code "68") (name "SPI5_IRQ") (class "Default")
      (node (ref "X4") (pin "9") (pinfunction "1_9") (pintype "passive"))
      (node (ref "X7") (pin "10") (pinfunction "1_10") (pintype "passive"))
    )
    (net (code "69") (name "SPI5_MISO") (class "Default")
      (node (ref "X4") (pin "18") (pinfunction "1_18") (pintype "passive"))
      (node (ref "X7") (pin "14") (pinfunction "1_14") (pintype "passive"))
    )
    (net (code "70") (name "SPI5_MOSI") (class "Default")
      (node (ref "X4") (pin "20") (pinfunction "1_20") (pintype "passive"))
      (node (ref "X7") (pin "15") (pinfunction "1_15") (pintype "passive"))
    )
    (net (code "71") (name "UART_RX") (class "Default")
      (node (ref "X4") (pin "3") (pinfunction "1_3") (pintype "passive"))
      (node (ref "X5") (pin "27") (pinfunction "1_27") (pintype "passive"))
      (node (ref "X6") (pin "27") (pinfunction "1_27") (pintype "passive"))
      (node (ref "X7") (pin "27") (pinfunction "1_27") (pintype "passive"))
    )
    (net (code "72") (name "UART_TX") (class "Default")
      (node (ref "X4") (pin "4") (pinfunction "1_4") (pintype "passive"))
      (node (ref "X5") (pin "28") (pinfunction "1_28") (pintype "passive"))
      (node (ref "X6") (pin "28") (pinfunction "1_28") (pintype "passive"))
      (node (ref "X7") (pin "28") (pinfunction "1_28") (pintype "passive"))
    )
    (net (code "73") (name "unconnected-(IC1-~{INT}-Pad13)") (class "Default")
      (node (ref "IC1") (pin "13") (pinfunction "~{INT}_13") (pintype "output"))
    )
    (net (code "74") (name "unconnected-(K1A-S-Pad12A)") (class "Default")
      (node (ref "K1") (pin "12A") (pinfunction "S_12A") (pintype "passive"))
    )
    (net (code "75") (name "unconnected-(K1B-S-Pad12B)") (class "Default")
      (node (ref "K1") (pin "12B") (pinfunction "S_12B") (pintype "passive"))
    )
    (net (code "76") (name "unconnected-(K2A-S-Pad12A)") (class "Default")
      (node (ref "K2") (pin "12A") (pinfunction "S_12A") (pintype "passive"))
    )
    (net (code "77") (name "unconnected-(X5M-1-Pad20)") (class "Default")
      (node (ref "X5") (pin "20") (pinfunction "1_20") (pintype "passive"))
    )
    (net (code "78") (name "unconnected-(X6M-1-Pad20)") (class "Default")
      (node (ref "X6") (pin "20") (pinfunction "1_20") (pintype "passive"))
    )
    (net (code "79") (name "unconnected-(X7M-1-Pad20)") (class "Default")
      (node (ref "X7") (pin "20") (pinfunction "1_20") (pintype "passive"))
    )
    (net (code "80") (name "~{FAULT}") (class "Default")
      (node (ref "X4") (pin "8") (pinfunction "1_8") (pintype "passive"))
      (node (ref "X5") (pin "3") (pinfunction "1_3") (pintype "passive"))
      (node (ref "X6") (pin "3") (pinfunction "1_3") (pintype "passive"))
      (node (ref "X7") (pin "3") (pinfunction "1_3") (pintype "passive"))
    )
    (net (code "81") (name "~{MRESET}") (class "Default")
      (node (ref "D8") (pin "C") (pinfunction "C_C") (pintype "passive"))
      (node (ref "X4") (pin "6") (pinfunction "1_6") (pintype "passive"))
    )
    (net (code "82") (name "~{RESET}") (class "Default")
      (node (ref "C2") (pin "1") (pinfunction "1_1") (pintype "passive"))
      (node (ref "D7") (pin "A") (pinfunction "A_A") (pintype "passive"))
      (node (ref "D8") (pin "A") (pinfunction "A_A") (pintype "passive"))
      (node (ref "R9") (pin "2") (pinfunction "2_2") (pintype "passive"))
      (node (ref "X5") (pin "4") (pinfunction "1_4") (pintype "passive"))
      (node (ref "X6") (pin "4") (pinfunction "1_4") (pintype "passive"))
      (node (ref "X7") (pin "4") (pinfunction "1_4") (pintype "passive"))
    )
  )
)
